# Patch_panel_module_rev2.net
KiCad netlist of a schematic drawn in EAGLE
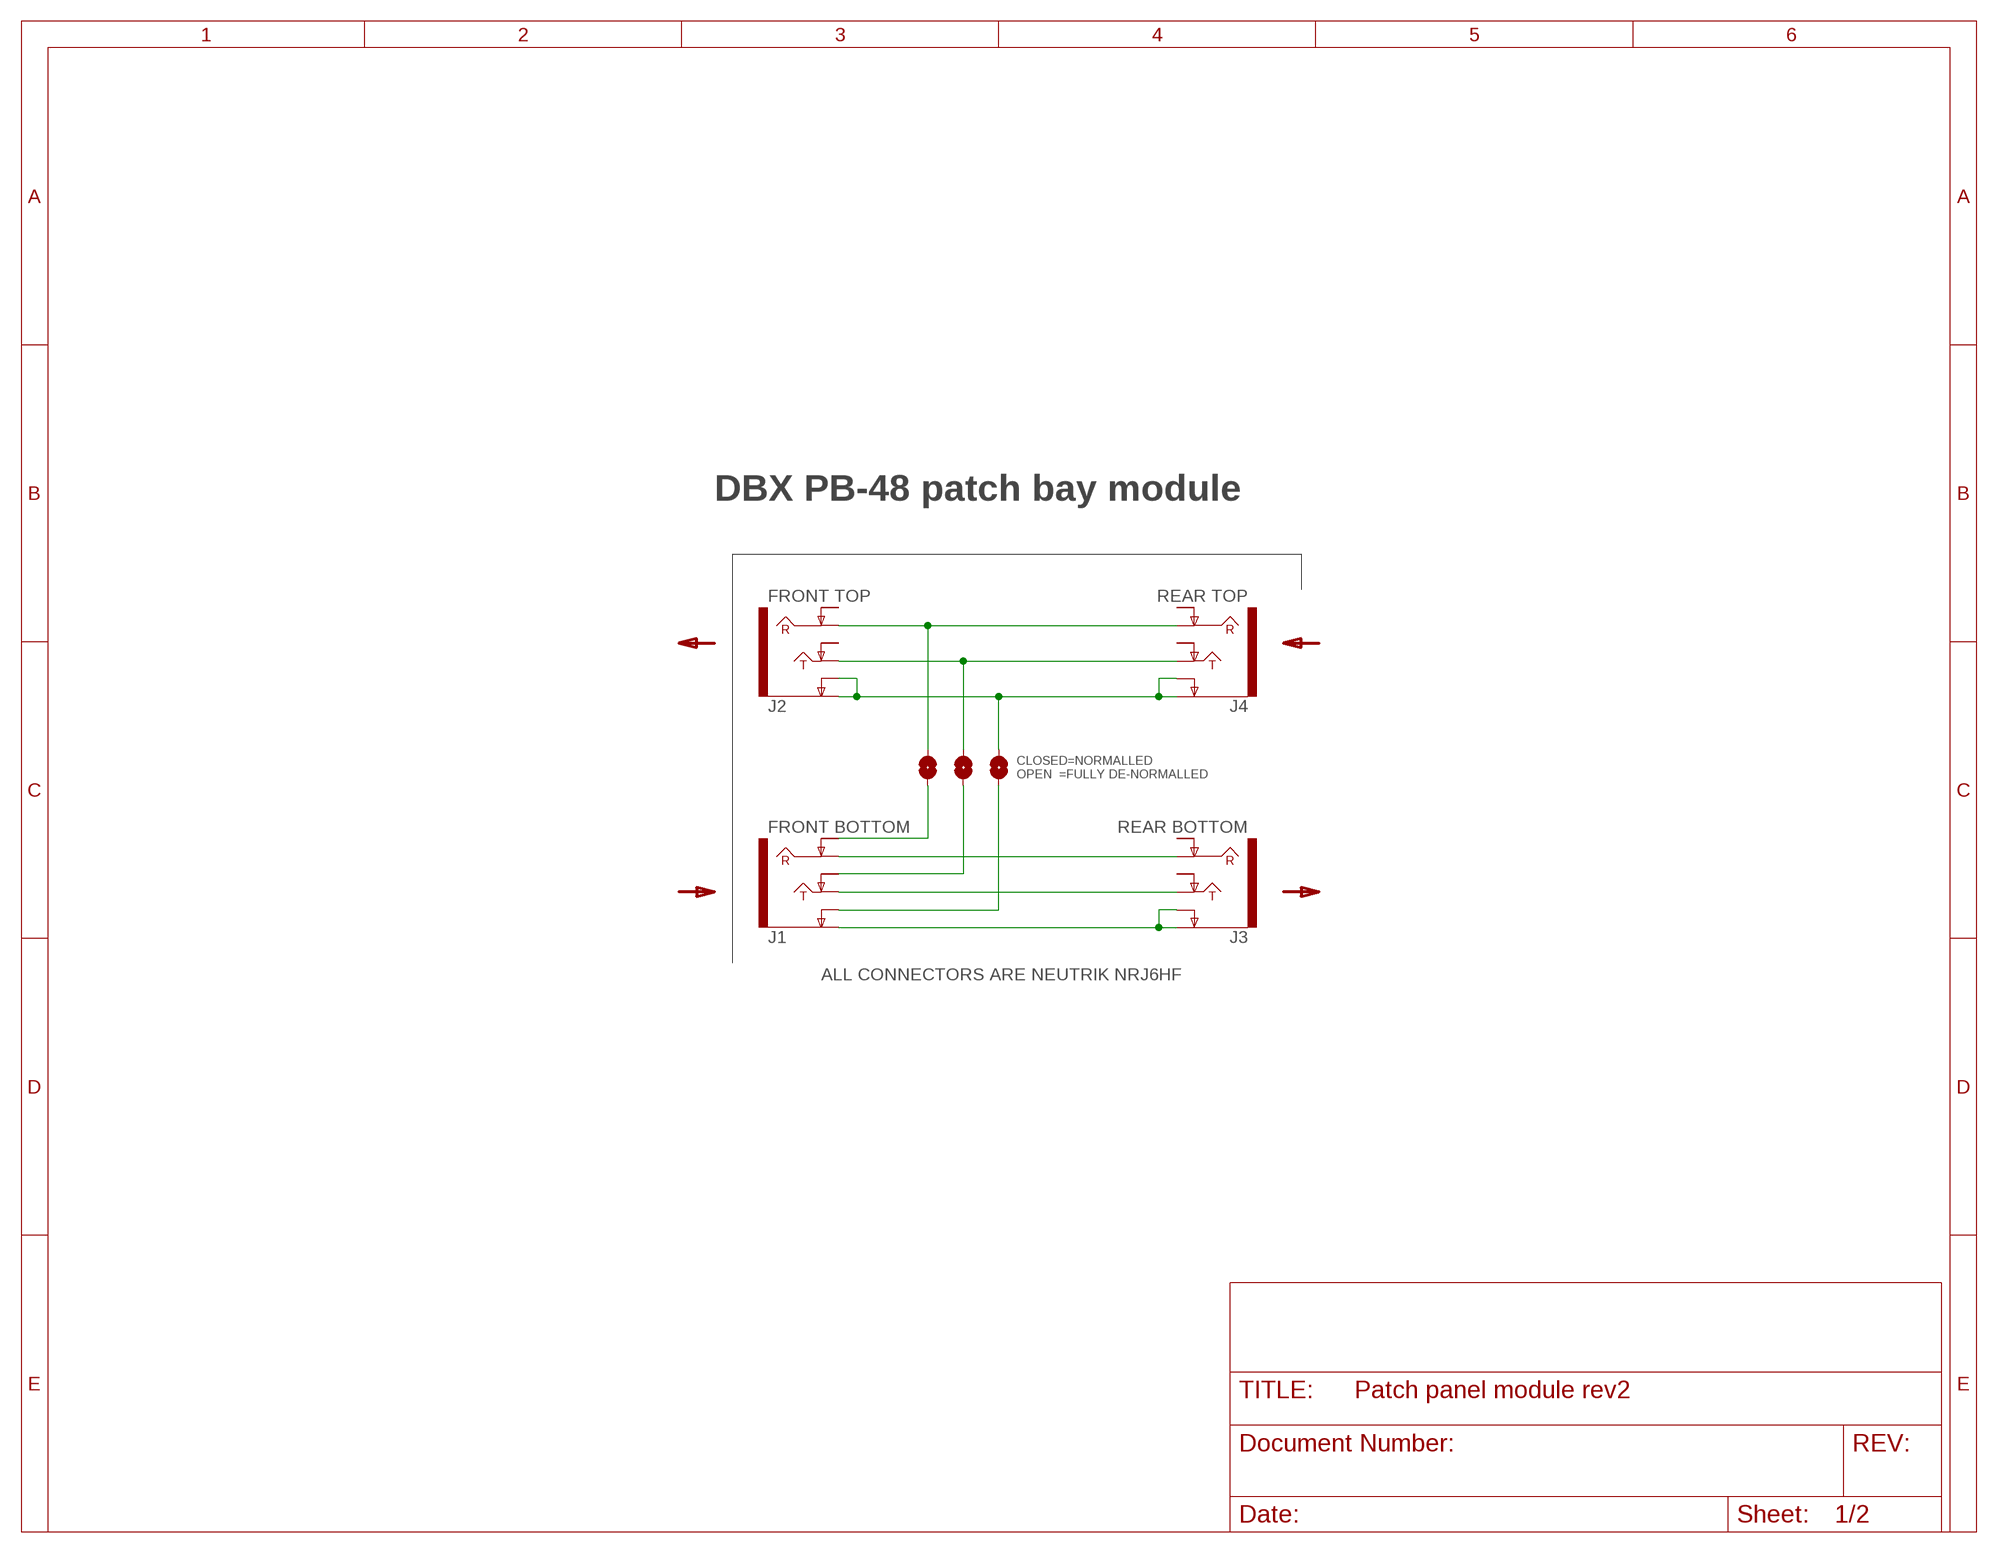
[diagram p0: schematic, sheet 1]
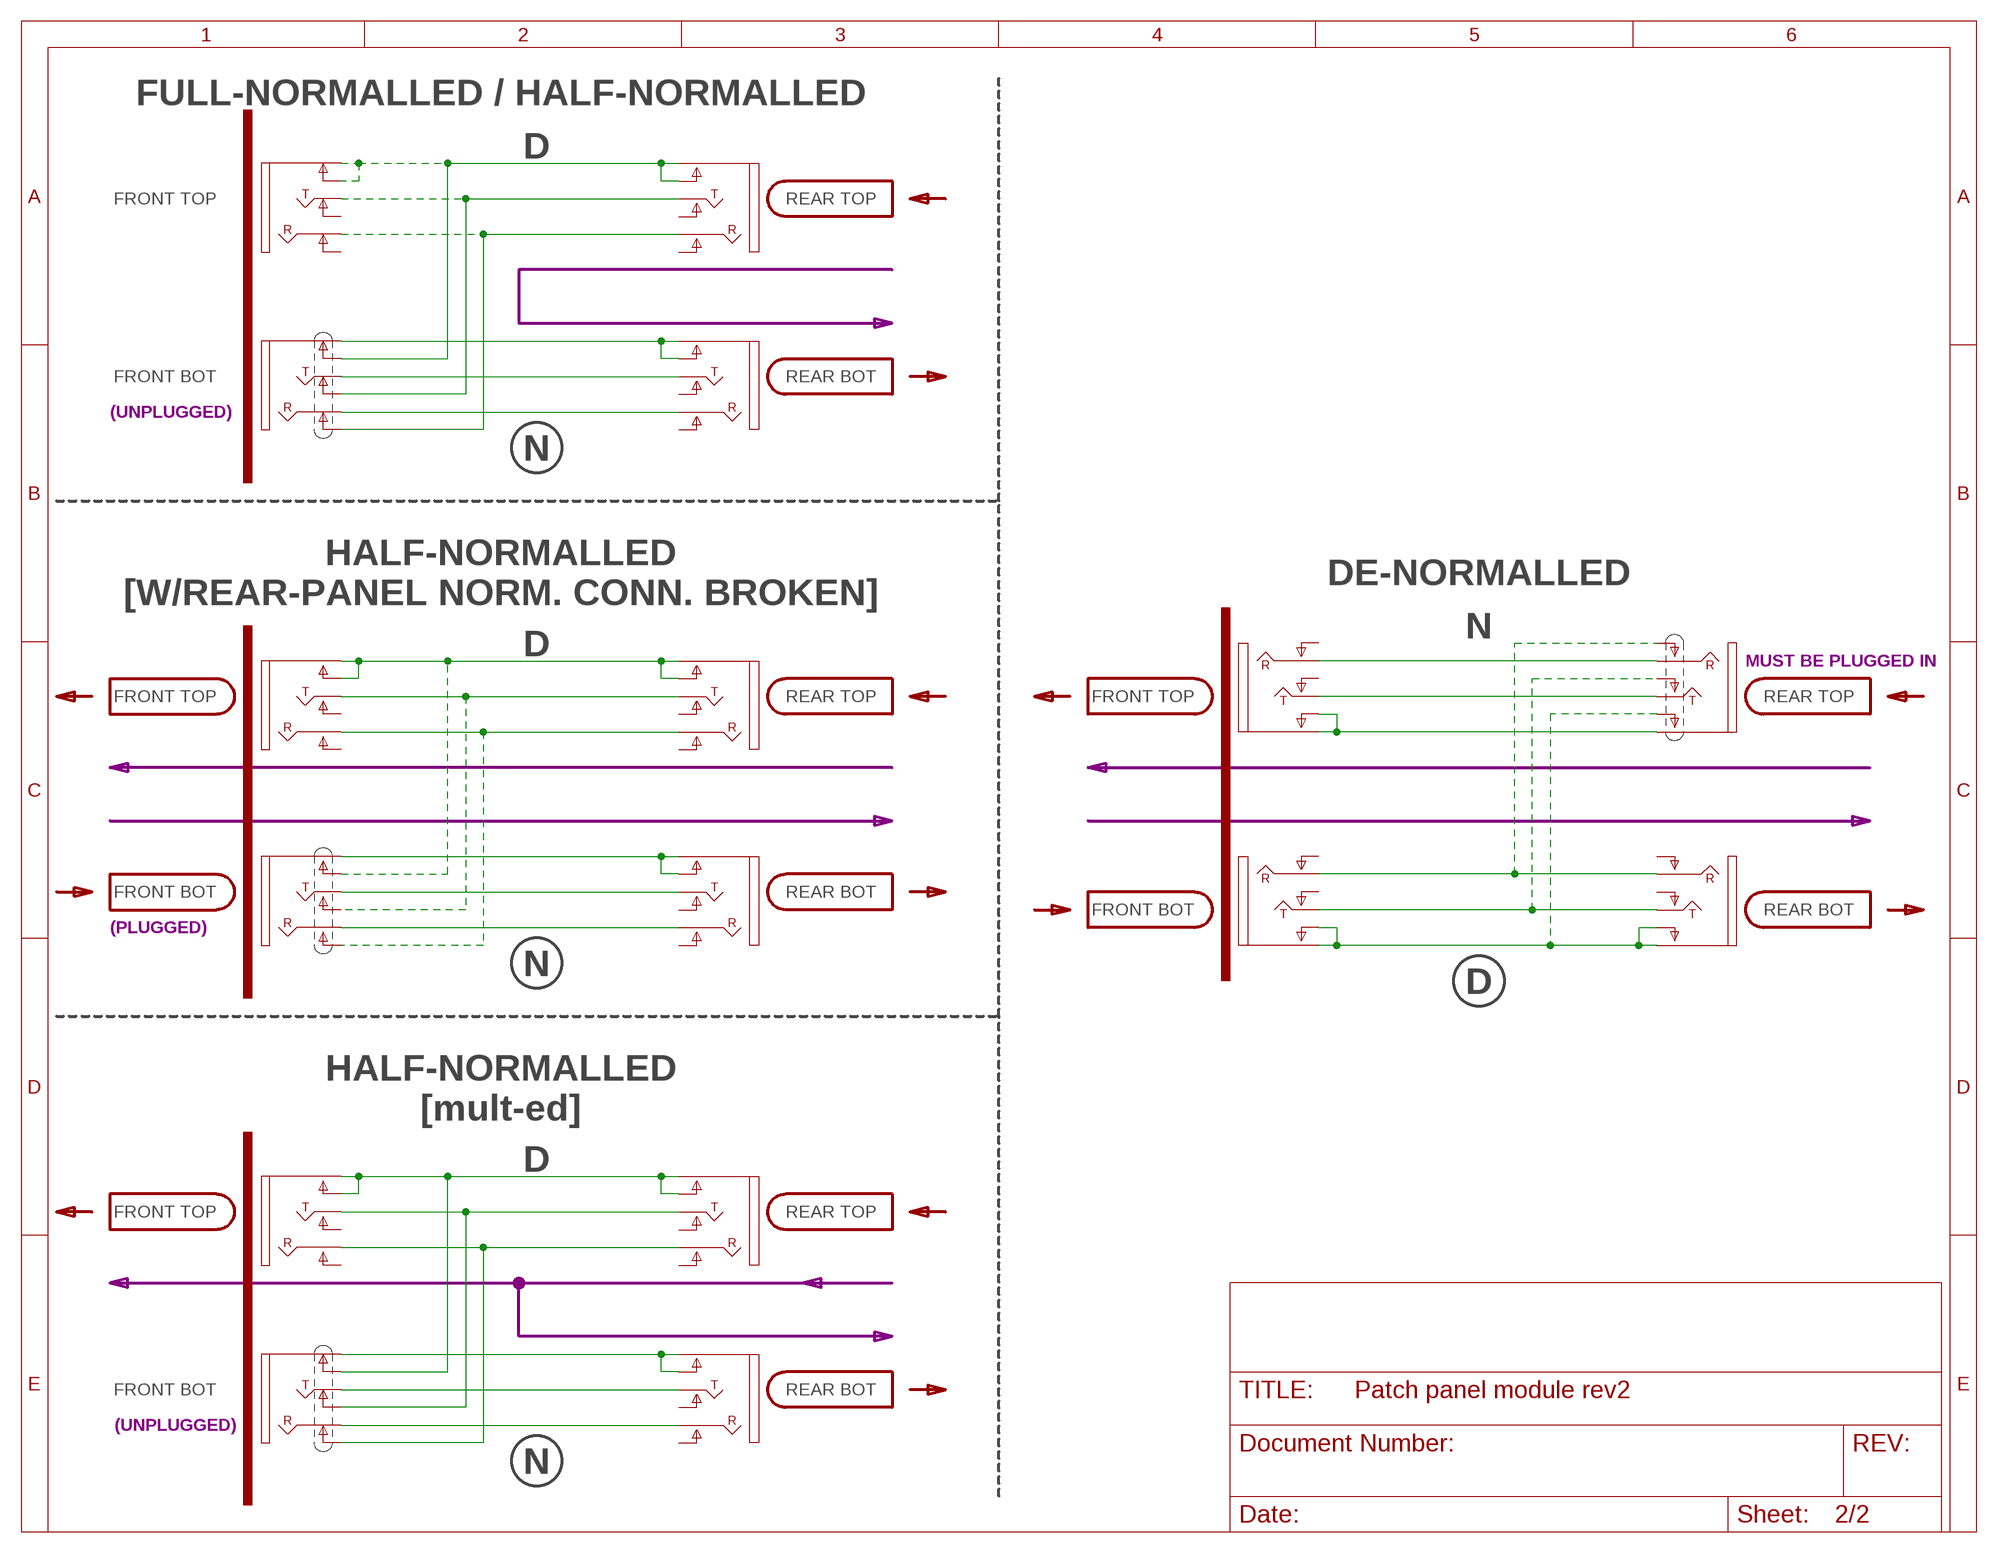
[diagram p1: schematic, sheet 2]

(export (version "E")
  (design (tool "Eeschema 10.0.6"))
  (components
    (comp (ref "J1")
      (value "FRONT BOTTOM")
      (footprint "eagle-import:NEUTRIK-NRJ6HF")
      (libsource (lib "eagle-import") (part "AUDIO_JACK_TRS_0.25{dblquote}_PTH_RA-NRJ6HM"))
    )
    (comp (ref "J2")
      (value "FRONT TOP")
      (footprint "eagle-import:NEUTRIK-NRJ6HF")
      (libsource (lib "eagle-import") (part "AUDIO_JACK_TRS_0.25{dblquote}_PTH_RA-NRJ6HM"))
    )
    (comp (ref "J3")
      (value "REAR BOTTOM")
      (footprint "eagle-import:NEUTRIK-NRJ6HF")
      (libsource (lib "eagle-import") (part "AUDIO_JACK_TRS_0.25{dblquote}_PTH_RA-NRJ6HM"))
    )
    (comp (ref "J4")
      (value "REAR TOP")
      (footprint "eagle-import:NEUTRIK-NRJ6HF")
      (libsource (lib "eagle-import") (part "AUDIO_JACK_TRS_0.25{dblquote}_PTH_RA-NRJ6HM"))
    )
    (comp (ref "JP1")
      (value "JUMPER-SMT_2_NO_NO-SILK_ROUND")
      (footprint "eagle-import:SMT-JUMPER_2_NO_NO-SILK_ROUND")
      (libsource (lib "eagle-import") (part "JUMPER-SMT_2_NO_NO-SILK_ROUND"))
    )
    (comp (ref "JP2")
      (value "JUMPER-SMT_2_NO_NO-SILK_ROUND")
      (footprint "eagle-import:SMT-JUMPER_2_NO_NO-SILK_ROUND")
      (libsource (lib "eagle-import") (part "JUMPER-SMT_2_NO_NO-SILK_ROUND"))
    )
    (comp (ref "JP3")
      (value "JUMPER-SMT_2_NO_NO-SILK_ROUND")
      (footprint "eagle-import:SMT-JUMPER_2_NO_NO-SILK_ROUND")
      (libsource (lib "eagle-import") (part "JUMPER-SMT_2_NO_NO-SILK_ROUND"))
    )
  )
  (nets
    (net (code "1") (name "Net-(J1-EARTH)") (class "Default")
      (node (ref "J1") (pin "S") (pinfunction "EARTH_S") (pintype "bidirectional"))
      (node (ref "J3") (pin "S") (pinfunction "EARTH_S") (pintype "bidirectional"))
      (node (ref "J3") (pin "SN") (pinfunction "EARTH-NORM_SN") (pintype "bidirectional"))
    )
    (net (code "2") (name "Net-(J1-EARTH-NORM)") (class "Default")
      (node (ref "J1") (pin "SN") (pinfunction "EARTH-NORM_SN") (pintype "bidirectional"))
      (node (ref "JP1") (pin "2") (pinfunction "2_2") (pintype "passive"))
    )
    (net (code "3") (name "Net-(J1-RING)") (class "Default")
      (node (ref "J1") (pin "R") (pinfunction "RING_R") (pintype "bidirectional"))
      (node (ref "J3") (pin "R") (pinfunction "RING_R") (pintype "bidirectional"))
    )
    (net (code "4") (name "Net-(J1-RING-NORM)") (class "Default")
      (node (ref "J1") (pin "RN") (pinfunction "RING-NORM_RN") (pintype "bidirectional"))
      (node (ref "JP3") (pin "2") (pinfunction "2_2") (pintype "passive"))
    )
    (net (code "5") (name "Net-(J1-TIP)") (class "Default")
      (node (ref "J1") (pin "T") (pinfunction "TIP_T") (pintype "bidirectional"))
      (node (ref "J3") (pin "T") (pinfunction "TIP_T") (pintype "bidirectional"))
    )
    (net (code "6") (name "Net-(J1-TIP-NORM)") (class "Default")
      (node (ref "J1") (pin "TN") (pinfunction "TIP-NORM_TN") (pintype "bidirectional"))
      (node (ref "JP2") (pin "2") (pinfunction "2_2") (pintype "passive"))
    )
    (net (code "7") (name "Net-(J2-EARTH)") (class "Default")
      (node (ref "J2") (pin "S") (pinfunction "EARTH_S") (pintype "bidirectional"))
      (node (ref "J2") (pin "SN") (pinfunction "EARTH-NORM_SN") (pintype "bidirectional"))
      (node (ref "J4") (pin "S") (pinfunction "EARTH_S") (pintype "bidirectional"))
      (node (ref "J4") (pin "SN") (pinfunction "EARTH-NORM_SN") (pintype "bidirectional"))
      (node (ref "JP1") (pin "1") (pinfunction "1_1") (pintype "passive"))
    )
    (net (code "8") (name "Net-(J2-RING)") (class "Default")
      (node (ref "J2") (pin "R") (pinfunction "RING_R") (pintype "bidirectional"))
      (node (ref "J4") (pin "R") (pinfunction "RING_R") (pintype "bidirectional"))
      (node (ref "JP3") (pin "1") (pinfunction "1_1") (pintype "passive"))
    )
    (net (code "9") (name "Net-(J2-TIP)") (class "Default")
      (node (ref "J2") (pin "T") (pinfunction "TIP_T") (pintype "bidirectional"))
      (node (ref "J4") (pin "T") (pinfunction "TIP_T") (pintype "bidirectional"))
      (node (ref "JP2") (pin "1") (pinfunction "1_1") (pintype "passive"))
    )
    (net (code "10") (name "unconnected-(J2-RING-NORM-PadRN)") (class "Default")
      (node (ref "J2") (pin "RN") (pinfunction "RING-NORM_RN") (pintype "bidirectional"))
    )
    (net (code "11") (name "unconnected-(J2-TIP-NORM-PadTN)") (class "Default")
      (node (ref "J2") (pin "TN") (pinfunction "TIP-NORM_TN") (pintype "bidirectional"))
    )
    (net (code "12") (name "unconnected-(J3-RING-NORM-PadRN)") (class "Default")
      (node (ref "J3") (pin "RN") (pinfunction "RING-NORM_RN") (pintype "bidirectional"))
    )
    (net (code "13") (name "unconnected-(J3-TIP-NORM-PadTN)") (class "Default")
      (node (ref "J3") (pin "TN") (pinfunction "TIP-NORM_TN") (pintype "bidirectional"))
    )
    (net (code "14") (name "unconnected-(J4-RING-NORM-PadRN)") (class "Default")
      (node (ref "J4") (pin "RN") (pinfunction "RING-NORM_RN") (pintype "bidirectional"))
    )
    (net (code "15") (name "unconnected-(J4-TIP-NORM-PadTN)") (class "Default")
      (node (ref "J4") (pin "TN") (pinfunction "TIP-NORM_TN") (pintype "bidirectional"))
    )
  )
)
